# SkyMap.net
KiCad netlist of a schematic drawn in EAGLE
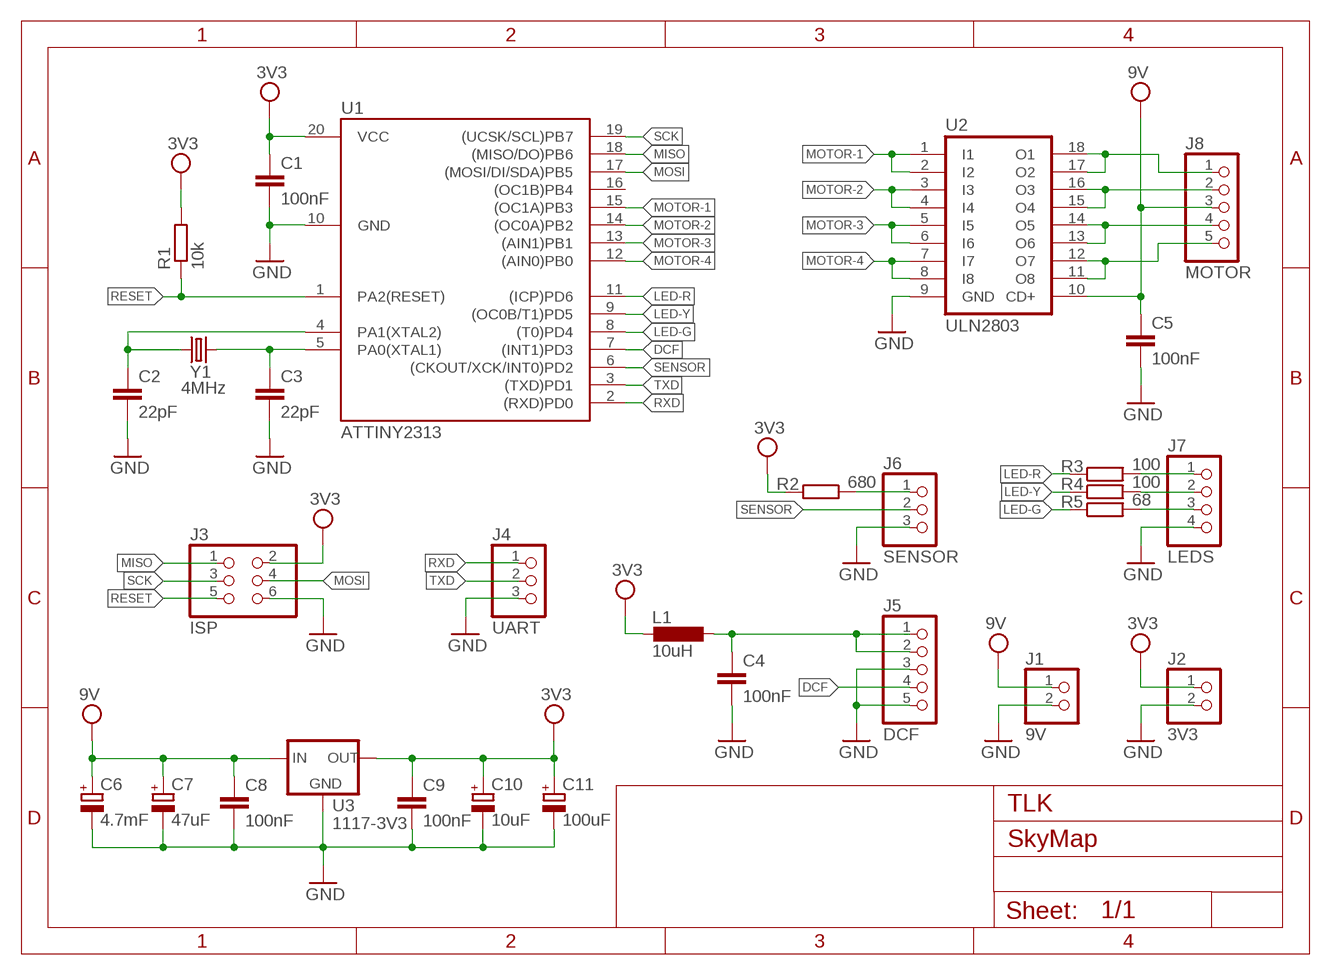
[diagram p0: schematic, sheet 1]

(export (version "E")
  (design (tool "Eeschema 10.0.6"))
  (components
    (comp (ref "C1")
      (value "100nF")
      (footprint "eagle-import:C050-025X075")
      (libsource (lib "eagle-import") (part "C-EU050-025X075"))
    )
    (comp (ref "C2")
      (value "22pF")
      (footprint "eagle-import:C025-025X050")
      (libsource (lib "eagle-import") (part "C-EU025-025X050"))
    )
    (comp (ref "C3")
      (value "22pF")
      (footprint "eagle-import:C025-025X050")
      (libsource (lib "eagle-import") (part "C-EU025-025X050"))
    )
    (comp (ref "C4")
      (value "100nF")
      (footprint "eagle-import:C025-025X050")
      (libsource (lib "eagle-import") (part "C-EU025-025X050"))
    )
    (comp (ref "C5")
      (value "100nF")
      (footprint "eagle-import:C025-025X050")
      (libsource (lib "eagle-import") (part "C-EU025-025X050"))
    )
    (comp (ref "C6")
      (value "4.7mF")
      (footprint "eagle-import:E5-13")
      (libsource (lib "eagle-import") (part "CPOL-EUE5-13"))
    )
    (comp (ref "C7")
      (value "47uF")
      (footprint "eagle-import:E2,5-6")
      (libsource (lib "eagle-import") (part "CPOL-EUE2.5-6"))
    )
    (comp (ref "C8")
      (value "100nF")
      (footprint "eagle-import:C025-025X050")
      (libsource (lib "eagle-import") (part "C-EU025-025X050"))
    )
    (comp (ref "C9")
      (value "100nF")
      (footprint "eagle-import:C025-025X050")
      (libsource (lib "eagle-import") (part "C-EU025-025X050"))
    )
    (comp (ref "C10")
      (value "10uF")
      (footprint "eagle-import:E2,5-6")
      (libsource (lib "eagle-import") (part "CPOL-EUE2.5-6"))
    )
    (comp (ref "C11")
      (value "100uF")
      (footprint "eagle-import:E3,5-8")
      (libsource (lib "eagle-import") (part "CPOL-EUE3.5-8"))
    )
    (comp (ref "J1")
      (value "9V")
      (footprint "eagle-import:1X02")
      (libsource (lib "eagle-import") (part "PINHD-1X2"))
    )
    (comp (ref "J2")
      (value "3V3")
      (footprint "eagle-import:1X02")
      (libsource (lib "eagle-import") (part "PINHD-1X2"))
    )
    (comp (ref "J3")
      (value "ISP")
      (footprint "eagle-import:2X03")
      (libsource (lib "eagle-import") (part "PINHD-2X3"))
    )
    (comp (ref "J4")
      (value "UART")
      (footprint "eagle-import:1X03")
      (libsource (lib "eagle-import") (part "PINHD-1X3"))
    )
    (comp (ref "J5")
      (value "DCF")
      (footprint "eagle-import:1X05")
      (libsource (lib "eagle-import") (part "PINHD-1X5"))
    )
    (comp (ref "J6")
      (value "SENSOR")
      (footprint "eagle-import:1X03")
      (libsource (lib "eagle-import") (part "PINHD-1X3"))
    )
    (comp (ref "J7")
      (value "LEDS")
      (footprint "eagle-import:1X04")
      (libsource (lib "eagle-import") (part "PINHD-1X4"))
    )
    (comp (ref "J8")
      (value "MOTOR")
      (footprint "eagle-import:1X05")
      (libsource (lib "eagle-import") (part "PINHD-1X5"))
    )
    (comp (ref "L1")
      (value "10uH")
      (footprint "eagle-import:2200-12.7")
      (libsource (lib "eagle-import") (part "L-EU2200-12.7"))
    )
    (comp (ref "R1")
      (value "10k")
      (footprint "eagle-import:0207_7")
      (libsource (lib "eagle-import") (part "R-EU_0207/7"))
    )
    (comp (ref "R2")
      (value "680")
      (footprint "eagle-import:0207_7")
      (libsource (lib "eagle-import") (part "R-EU_0207/7"))
    )
    (comp (ref "R3")
      (value "100")
      (footprint "eagle-import:0207_7")
      (libsource (lib "eagle-import") (part "R-EU_0207/7"))
    )
    (comp (ref "R4")
      (value "100")
      (footprint "eagle-import:0207_7")
      (libsource (lib "eagle-import") (part "R-EU_0207/7"))
    )
    (comp (ref "R5")
      (value "68")
      (footprint "eagle-import:0207_7")
      (libsource (lib "eagle-import") (part "R-EU_0207/7"))
    )
    (comp (ref "U1")
      (value "ATTINY2313")
      (footprint "eagle-import:DIL20")
      (libsource (lib "eagle-import") (part "ATTINY2313"))
    )
    (comp (ref "U2")
      (value "ULN2803")
      (footprint "eagle-import:DIL18")
      (libsource (lib "eagle-import") (part "ULN2803A"))
    )
    (comp (ref "U3")
      (value "1117-3V3")
      (footprint "eagle-import:TO92")
      (libsource (lib "eagle-import") (part "LP2950?ACZ-3.3"))
    )
    (comp (ref "Y1")
      (value "4MHz")
      (footprint "eagle-import:HC49_S")
      (libsource (lib "eagle-import") (part "CRYSTALHC49S"))
    )
  )
  (nets
    (net (code "1") (name "3V3") (class "Default")
      (node (ref "C1") (pin "1") (pinfunction "1_1") (pintype "passive"))
      (node (ref "C10") (pin "+") (pinfunction "+_+") (pintype "passive"))
      (node (ref "C11") (pin "+") (pinfunction "+_+") (pintype "passive"))
      (node (ref "C9") (pin "1") (pinfunction "1_1") (pintype "passive"))
      (node (ref "J2") (pin "1") (pinfunction "1_1") (pintype "passive"))
      (node (ref "J3") (pin "2") (pinfunction "2_2") (pintype "passive"))
      (node (ref "L1") (pin "2") (pinfunction "2_2") (pintype "passive"))
      (node (ref "R1") (pin "2") (pinfunction "2_2") (pintype "passive"))
      (node (ref "R2") (pin "2") (pinfunction "2_2") (pintype "passive"))
      (node (ref "U1") (pin "20") (pinfunction "VCC_20") (pintype "power_in"))
      (node (ref "U3") (pin "1") (pinfunction "OUT_1") (pintype "passive"))
    )
    (net (code "2") (name "9V") (class "Default")
      (node (ref "C5") (pin "1") (pinfunction "1_1") (pintype "passive"))
      (node (ref "C6") (pin "+") (pinfunction "+_+") (pintype "passive"))
      (node (ref "C7") (pin "+") (pinfunction "+_+") (pintype "passive"))
      (node (ref "C8") (pin "1") (pinfunction "1_1") (pintype "passive"))
      (node (ref "J1") (pin "1") (pinfunction "1_1") (pintype "passive"))
      (node (ref "J8") (pin "3") (pinfunction "3_3") (pintype "passive"))
      (node (ref "U2") (pin "10") (pinfunction "CD+_10") (pintype "passive"))
      (node (ref "U3") (pin "3") (pinfunction "IN_3") (pintype "input"))
    )
    (net (code "3") (name "DCF") (class "Default")
      (node (ref "J5") (pin "4") (pinfunction "4_4") (pintype "passive"))
      (node (ref "U1") (pin "7") (pinfunction "(INT1)PD3_7") (pintype "bidirectional"))
    )
    (net (code "4") (name "GND") (class "Default")
      (node (ref "C1") (pin "2") (pinfunction "2_2") (pintype "passive"))
      (node (ref "C10") (pin "-") (pinfunction "-_-") (pintype "passive"))
      (node (ref "C11") (pin "-") (pinfunction "-_-") (pintype "passive"))
      (node (ref "C2") (pin "2") (pinfunction "2_2") (pintype "passive"))
      (node (ref "C3") (pin "2") (pinfunction "2_2") (pintype "passive"))
      (node (ref "C4") (pin "2") (pinfunction "2_2") (pintype "passive"))
      (node (ref "C5") (pin "2") (pinfunction "2_2") (pintype "passive"))
      (node (ref "C6") (pin "-") (pinfunction "-_-") (pintype "passive"))
      (node (ref "C7") (pin "-") (pinfunction "-_-") (pintype "passive"))
      (node (ref "C8") (pin "2") (pinfunction "2_2") (pintype "passive"))
      (node (ref "C9") (pin "2") (pinfunction "2_2") (pintype "passive"))
      (node (ref "J1") (pin "2") (pinfunction "2_2") (pintype "passive"))
      (node (ref "J2") (pin "2") (pinfunction "2_2") (pintype "passive"))
      (node (ref "J3") (pin "6") (pinfunction "6_6") (pintype "passive"))
      (node (ref "J4") (pin "3") (pinfunction "3_3") (pintype "passive"))
      (node (ref "J5") (pin "3") (pinfunction "3_3") (pintype "passive"))
      (node (ref "J5") (pin "5") (pinfunction "5_5") (pintype "passive"))
      (node (ref "J6") (pin "3") (pinfunction "3_3") (pintype "passive"))
      (node (ref "J7") (pin "4") (pinfunction "4_4") (pintype "passive"))
      (node (ref "U1") (pin "10") (pinfunction "GND_10") (pintype "power_in"))
      (node (ref "U2") (pin "9") (pinfunction "GND_9") (pintype "power_in"))
      (node (ref "U3") (pin "2") (pinfunction "GND_2") (pintype "input"))
    )
    (net (code "5") (name "LED-G") (class "Default")
      (node (ref "R5") (pin "1") (pinfunction "1_1") (pintype "passive"))
      (node (ref "U1") (pin "8") (pinfunction "(T0)PD4_8") (pintype "bidirectional"))
    )
    (net (code "6") (name "LED-R") (class "Default")
      (node (ref "R3") (pin "1") (pinfunction "1_1") (pintype "passive"))
      (node (ref "U1") (pin "11") (pinfunction "(ICP)PD6_11") (pintype "bidirectional"))
    )
    (net (code "7") (name "LED-Y") (class "Default")
      (node (ref "R4") (pin "1") (pinfunction "1_1") (pintype "passive"))
      (node (ref "U1") (pin "9") (pinfunction "(OC0B/T1)PD5_9") (pintype "bidirectional"))
    )
    (net (code "8") (name "MISO") (class "Default")
      (node (ref "J3") (pin "1") (pinfunction "1_1") (pintype "passive"))
      (node (ref "U1") (pin "18") (pinfunction "(MISO/DO)PB6_18") (pintype "bidirectional"))
    )
    (net (code "9") (name "MOSI") (class "Default")
      (node (ref "J3") (pin "4") (pinfunction "4_4") (pintype "passive"))
      (node (ref "U1") (pin "17") (pinfunction "(MOSI/DI/SDA)PB5_17") (pintype "bidirectional"))
    )
    (net (code "10") (name "MOTOR-1") (class "Default")
      (node (ref "U1") (pin "15") (pinfunction "(OC1A)PB3_15") (pintype "bidirectional"))
      (node (ref "U2") (pin "1") (pinfunction "I1_1") (pintype "input"))
      (node (ref "U2") (pin "2") (pinfunction "I2_2") (pintype "input"))
    )
    (net (code "11") (name "MOTOR-2") (class "Default")
      (node (ref "U1") (pin "14") (pinfunction "(OC0A)PB2_14") (pintype "bidirectional"))
      (node (ref "U2") (pin "3") (pinfunction "I3_3") (pintype "input"))
      (node (ref "U2") (pin "4") (pinfunction "I4_4") (pintype "input"))
    )
    (net (code "12") (name "MOTOR-3") (class "Default")
      (node (ref "U1") (pin "13") (pinfunction "(AIN1)PB1_13") (pintype "bidirectional"))
      (node (ref "U2") (pin "5") (pinfunction "I5_5") (pintype "input"))
      (node (ref "U2") (pin "6") (pinfunction "I6_6") (pintype "input"))
    )
    (net (code "13") (name "MOTOR-4") (class "Default")
      (node (ref "U1") (pin "12") (pinfunction "(AIN0)PB0_12") (pintype "bidirectional"))
      (node (ref "U2") (pin "7") (pinfunction "I7_7") (pintype "input"))
      (node (ref "U2") (pin "8") (pinfunction "I8_8") (pintype "input"))
    )
    (net (code "14") (name "Net-(C4-Pad1)") (class "Default")
      (node (ref "C4") (pin "1") (pinfunction "1_1") (pintype "passive"))
      (node (ref "J5") (pin "1") (pinfunction "1_1") (pintype "passive"))
      (node (ref "J5") (pin "2") (pinfunction "2_2") (pintype "passive"))
      (node (ref "L1") (pin "1") (pinfunction "1_1") (pintype "passive"))
    )
    (net (code "15") (name "Net-(J6-Pad1)") (class "Default")
      (node (ref "J6") (pin "1") (pinfunction "1_1") (pintype "passive"))
      (node (ref "R2") (pin "1") (pinfunction "1_1") (pintype "passive"))
    )
    (net (code "16") (name "Net-(J7-Pad1)") (class "Default")
      (node (ref "J7") (pin "1") (pinfunction "1_1") (pintype "passive"))
      (node (ref "R3") (pin "2") (pinfunction "2_2") (pintype "passive"))
    )
    (net (code "17") (name "Net-(J7-Pad2)") (class "Default")
      (node (ref "J7") (pin "2") (pinfunction "2_2") (pintype "passive"))
      (node (ref "R4") (pin "2") (pinfunction "2_2") (pintype "passive"))
    )
    (net (code "18") (name "Net-(J7-Pad3)") (class "Default")
      (node (ref "J7") (pin "3") (pinfunction "3_3") (pintype "passive"))
      (node (ref "R5") (pin "2") (pinfunction "2_2") (pintype "passive"))
    )
    (net (code "19") (name "Net-(U1-PA0(XTAL1))") (class "Default")
      (node (ref "C3") (pin "1") (pinfunction "1_1") (pintype "passive"))
      (node (ref "U1") (pin "5") (pinfunction "PA0(XTAL1)_5") (pintype "bidirectional"))
      (node (ref "Y1") (pin "2") (pinfunction "2_2") (pintype "passive"))
    )
    (net (code "20") (name "Net-(U1-PA1(XTAL2))") (class "Default")
      (node (ref "C2") (pin "1") (pinfunction "1_1") (pintype "passive"))
      (node (ref "U1") (pin "4") (pinfunction "PA1(XTAL2)_4") (pintype "bidirectional"))
      (node (ref "Y1") (pin "1") (pinfunction "1_1") (pintype "passive"))
    )
    (net (code "21") (name "Net-(U2-O1)") (class "Default")
      (node (ref "J8") (pin "1") (pinfunction "1_1") (pintype "passive"))
      (node (ref "U2") (pin "17") (pinfunction "O2_17") (pintype "open_collector"))
      (node (ref "U2") (pin "18") (pinfunction "O1_18") (pintype "open_collector"))
    )
    (net (code "22") (name "Net-(U2-O3)") (class "Default")
      (node (ref "J8") (pin "2") (pinfunction "2_2") (pintype "passive"))
      (node (ref "U2") (pin "15") (pinfunction "O4_15") (pintype "open_collector"))
      (node (ref "U2") (pin "16") (pinfunction "O3_16") (pintype "open_collector"))
    )
    (net (code "23") (name "Net-(U2-O5)") (class "Default")
      (node (ref "J8") (pin "4") (pinfunction "4_4") (pintype "passive"))
      (node (ref "U2") (pin "13") (pinfunction "O6_13") (pintype "open_collector"))
      (node (ref "U2") (pin "14") (pinfunction "O5_14") (pintype "open_collector"))
    )
    (net (code "24") (name "Net-(U2-O7)") (class "Default")
      (node (ref "J8") (pin "5") (pinfunction "5_5") (pintype "passive"))
      (node (ref "U2") (pin "11") (pinfunction "O8_11") (pintype "open_collector"))
      (node (ref "U2") (pin "12") (pinfunction "O7_12") (pintype "open_collector"))
    )
    (net (code "25") (name "RESET") (class "Default")
      (node (ref "J3") (pin "5") (pinfunction "5_5") (pintype "passive"))
      (node (ref "R1") (pin "1") (pinfunction "1_1") (pintype "passive"))
      (node (ref "U1") (pin "1") (pinfunction "PA2(RESET)_1") (pintype "bidirectional"))
    )
    (net (code "26") (name "RXD") (class "Default")
      (node (ref "J4") (pin "1") (pinfunction "1_1") (pintype "passive"))
      (node (ref "U1") (pin "2") (pinfunction "(RXD)PD0_2") (pintype "bidirectional"))
    )
    (net (code "27") (name "SCK") (class "Default")
      (node (ref "J3") (pin "3") (pinfunction "3_3") (pintype "passive"))
      (node (ref "U1") (pin "19") (pinfunction "(UCSK/SCL)PB7_19") (pintype "bidirectional"))
    )
    (net (code "28") (name "SENSOR") (class "Default")
      (node (ref "J6") (pin "2") (pinfunction "2_2") (pintype "passive"))
      (node (ref "U1") (pin "6") (pinfunction "(CKOUT/XCK/INT0)PD2_6") (pintype "bidirectional"))
    )
    (net (code "29") (name "TXD") (class "Default")
      (node (ref "J4") (pin "2") (pinfunction "2_2") (pintype "passive"))
      (node (ref "U1") (pin "3") (pinfunction "(TXD)PD1_3") (pintype "bidirectional"))
    )
    (net (code "30") (name "unconnected-(U1-(OC1B)PB4-Pad16)") (class "Default")
      (node (ref "U1") (pin "16") (pinfunction "(OC1B)PB4_16") (pintype "bidirectional"))
    )
  )
)
